# ASD2412.net
KiCad netlist of a schematic drawn in EAGLE
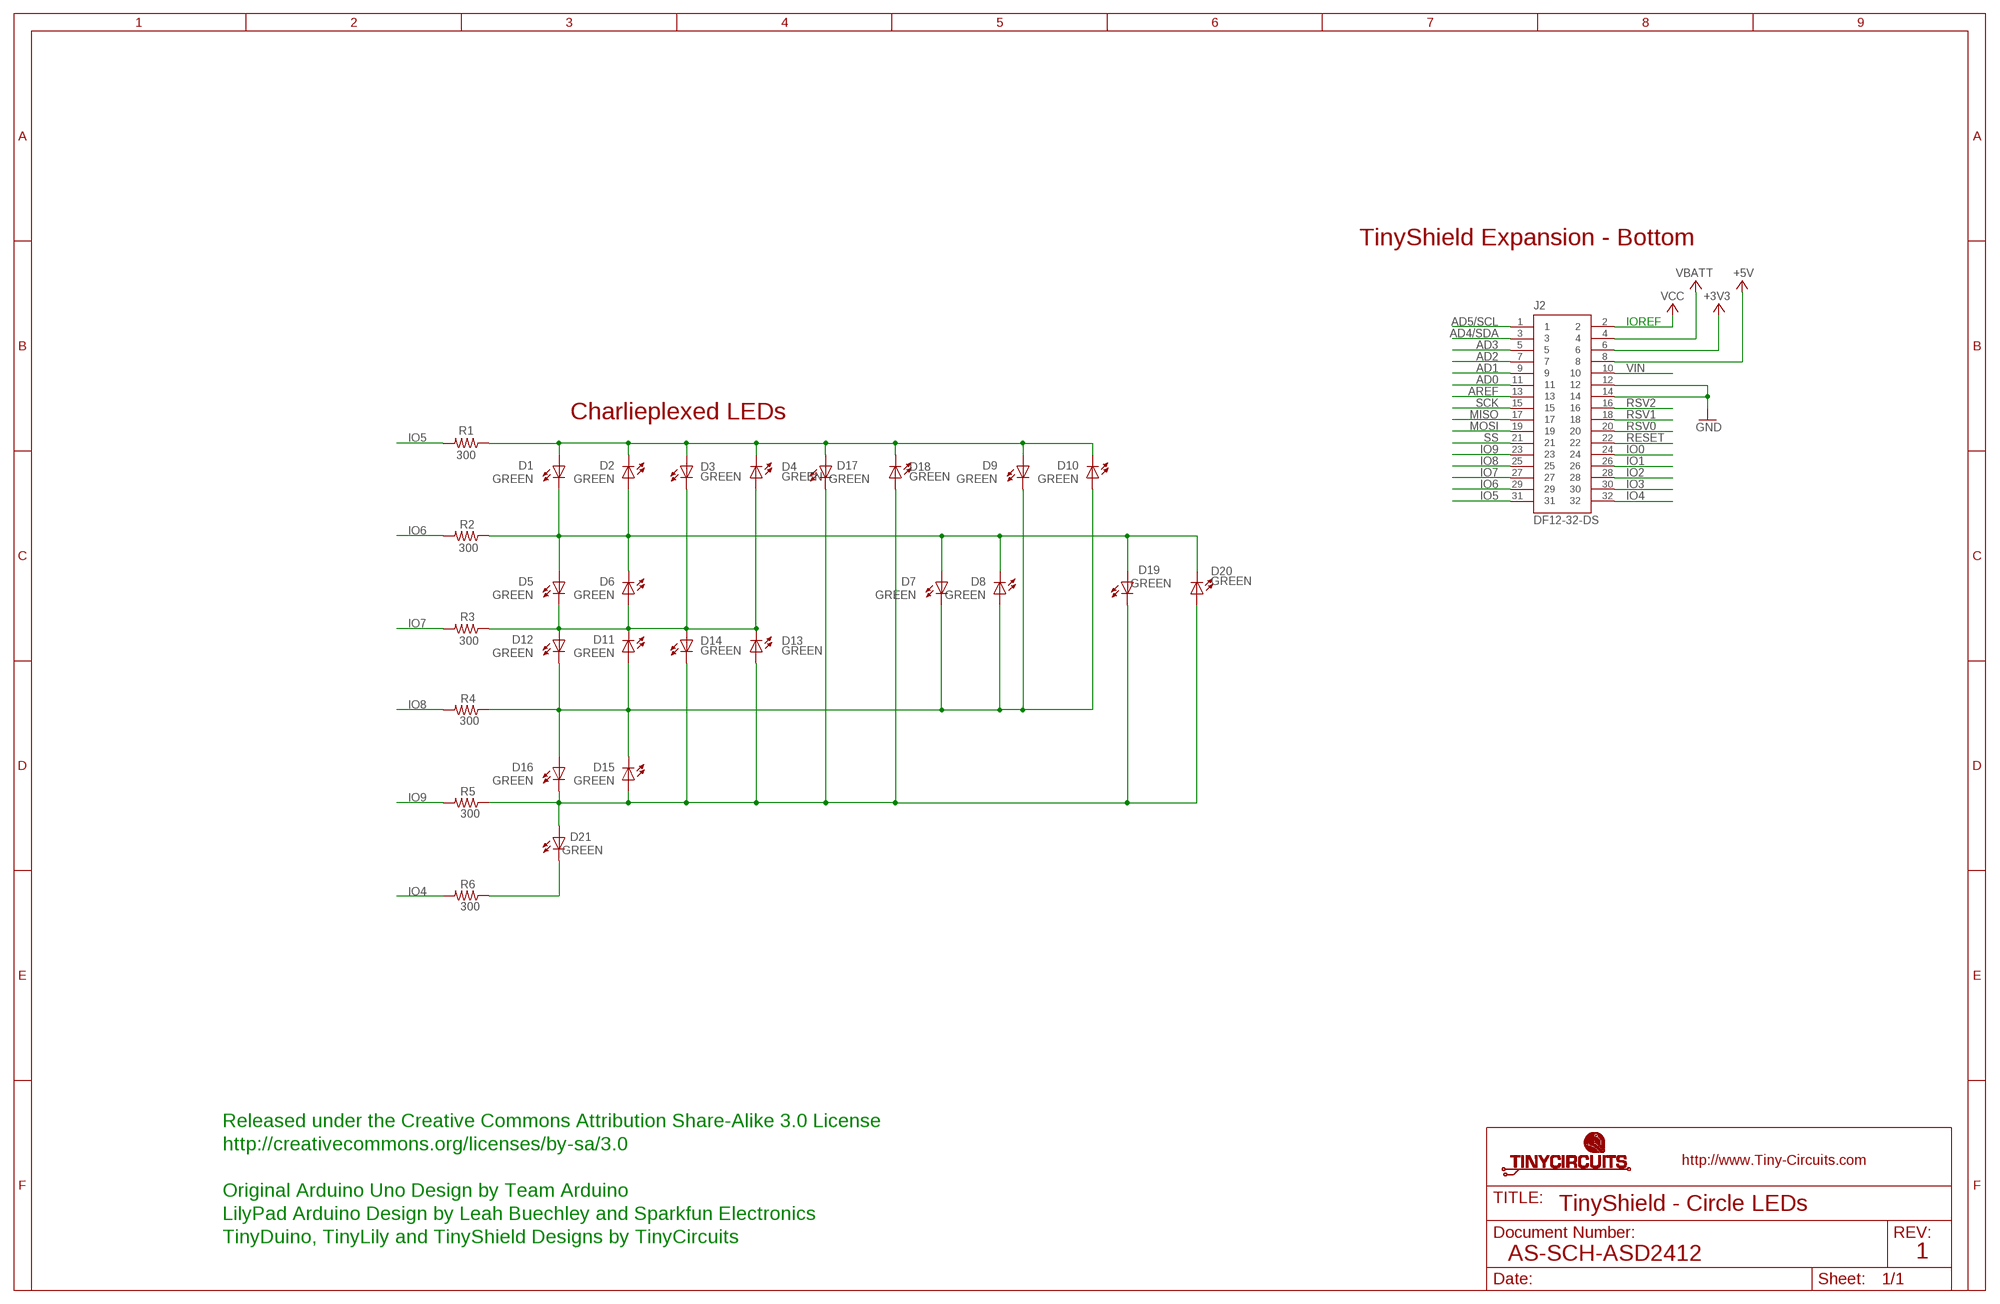
[diagram p0: schematic, sheet 1]

(export (version "E")
  (design (tool "Eeschema 10.0.6"))
  (components
    (comp (ref "D1")
      (value "GREEN")
      (footprint "eagle-import:LNJ_LED")
      (fields (field (name "PARTNO") "AS-ITM-00011") (field (name "PARTNO_1") "AS-ITM-00011"))
      (libsource (lib "eagle-import") (part "AS-ITM-00011"))
    )
    (comp (ref "D2")
      (value "GREEN")
      (footprint "eagle-import:LNJ_LED")
      (fields (field (name "PARTNO") "AS-ITM-00011") (field (name "PARTNO_1") "AS-ITM-00011"))
      (libsource (lib "eagle-import") (part "AS-ITM-00011"))
    )
    (comp (ref "D3")
      (value "GREEN")
      (footprint "eagle-import:LNJ_LED")
      (fields (field (name "PARTNO") "AS-ITM-00011") (field (name "PARTNO_1") "AS-ITM-00011"))
      (libsource (lib "eagle-import") (part "AS-ITM-00011"))
    )
    (comp (ref "D4")
      (value "GREEN")
      (footprint "eagle-import:LNJ_LED")
      (fields (field (name "PARTNO") "AS-ITM-00011") (field (name "PARTNO_1") "AS-ITM-00011"))
      (libsource (lib "eagle-import") (part "AS-ITM-00011"))
    )
    (comp (ref "D5")
      (value "GREEN")
      (footprint "eagle-import:LNJ_LED")
      (fields (field (name "PARTNO") "AS-ITM-00011") (field (name "PARTNO_1") "AS-ITM-00011"))
      (libsource (lib "eagle-import") (part "AS-ITM-00011"))
    )
    (comp (ref "D6")
      (value "GREEN")
      (footprint "eagle-import:LNJ_LED")
      (fields (field (name "PARTNO") "AS-ITM-00011") (field (name "PARTNO_1") "AS-ITM-00011"))
      (libsource (lib "eagle-import") (part "AS-ITM-00011"))
    )
    (comp (ref "D7")
      (value "GREEN")
      (footprint "eagle-import:LNJ_LED")
      (fields (field (name "PARTNO") "AS-ITM-00011") (field (name "PARTNO_1") "AS-ITM-00011"))
      (libsource (lib "eagle-import") (part "AS-ITM-00011"))
    )
    (comp (ref "D8")
      (value "GREEN")
      (footprint "eagle-import:LNJ_LED")
      (fields (field (name "PARTNO") "AS-ITM-00011") (field (name "PARTNO_1") "AS-ITM-00011"))
      (libsource (lib "eagle-import") (part "AS-ITM-00011"))
    )
    (comp (ref "D9")
      (value "GREEN")
      (footprint "eagle-import:LNJ_LED")
      (fields (field (name "PARTNO") "AS-ITM-00011") (field (name "PARTNO_1") "AS-ITM-00011"))
      (libsource (lib "eagle-import") (part "AS-ITM-00011"))
    )
    (comp (ref "D10")
      (value "GREEN")
      (footprint "eagle-import:LNJ_LED")
      (fields (field (name "PARTNO") "AS-ITM-00011") (field (name "PARTNO_1") "AS-ITM-00011"))
      (libsource (lib "eagle-import") (part "AS-ITM-00011"))
    )
    (comp (ref "D11")
      (value "GREEN")
      (footprint "eagle-import:LNJ_LED")
      (fields (field (name "PARTNO") "AS-ITM-00011") (field (name "PARTNO_1") "AS-ITM-00011"))
      (libsource (lib "eagle-import") (part "AS-ITM-00011"))
    )
    (comp (ref "D12")
      (value "GREEN")
      (footprint "eagle-import:LNJ_LED")
      (fields (field (name "PARTNO") "AS-ITM-00011") (field (name "PARTNO_1") "AS-ITM-00011"))
      (libsource (lib "eagle-import") (part "AS-ITM-00011"))
    )
    (comp (ref "D13")
      (value "GREEN")
      (footprint "eagle-import:LNJ_LED")
      (fields (field (name "PARTNO") "AS-ITM-00011") (field (name "PARTNO_1") "AS-ITM-00011"))
      (libsource (lib "eagle-import") (part "AS-ITM-00011"))
    )
    (comp (ref "D14")
      (value "GREEN")
      (footprint "eagle-import:LNJ_LED")
      (fields (field (name "PARTNO") "AS-ITM-00011") (field (name "PARTNO_1") "AS-ITM-00011"))
      (libsource (lib "eagle-import") (part "AS-ITM-00011"))
    )
    (comp (ref "D15")
      (value "GREEN")
      (footprint "eagle-import:LNJ_LED")
      (fields (field (name "PARTNO") "AS-ITM-00011") (field (name "PARTNO_1") "AS-ITM-00011"))
      (libsource (lib "eagle-import") (part "AS-ITM-00011"))
    )
    (comp (ref "D16")
      (value "GREEN")
      (footprint "eagle-import:LNJ_LED")
      (fields (field (name "PARTNO") "AS-ITM-00011") (field (name "PARTNO_1") "AS-ITM-00011"))
      (libsource (lib "eagle-import") (part "AS-ITM-00011"))
    )
    (comp (ref "D17")
      (value "GREEN")
      (footprint "eagle-import:LNJ_LED")
      (fields (field (name "PARTNO") "AS-ITM-00011"))
      (libsource (lib "eagle-import") (part "AS-ITM-00011"))
    )
    (comp (ref "D18")
      (value "GREEN")
      (footprint "eagle-import:LNJ_LED")
      (fields (field (name "PARTNO") "AS-ITM-00011"))
      (libsource (lib "eagle-import") (part "AS-ITM-00011"))
    )
    (comp (ref "D19")
      (value "GREEN")
      (footprint "eagle-import:LNJ_LED")
      (fields (field (name "PARTNO") "AS-ITM-00011"))
      (libsource (lib "eagle-import") (part "AS-ITM-00011"))
    )
    (comp (ref "D20")
      (value "GREEN")
      (footprint "eagle-import:LNJ_LED")
      (fields (field (name "PARTNO") "AS-ITM-00011"))
      (libsource (lib "eagle-import") (part "AS-ITM-00011"))
    )
    (comp (ref "D21")
      (value "GREEN")
      (footprint "eagle-import:LNJ_LED")
      (fields (field (name "PARTNO") "AS-ITM-00011"))
      (libsource (lib "eagle-import") (part "AS-ITM-00011"))
    )
    (comp (ref "J2")
      (value "DF12-32-DS")
      (footprint "eagle-import:DF12-32-DS")
      (fields (field (name "PARTNO") "AS-ITM-00012") (field (name "PARTNO_1") "AS-ITM-00012"))
      (libsource (lib "eagle-import") (part "AS-ITM-00012"))
    )
    (comp (ref "R1")
      (value "300")
      (footprint "eagle-import:0402")
      (fields (field (name "PARTNO") "AS-ITM-00016") (field (name "PARTNO_1") "AS-ITM-00016"))
      (libsource (lib "eagle-import") (part "AS-ITM-00016"))
    )
    (comp (ref "R2")
      (value "300")
      (footprint "eagle-import:0402")
      (fields (field (name "PARTNO") "AS-ITM-00016"))
      (libsource (lib "eagle-import") (part "AS-ITM-00016"))
    )
    (comp (ref "R3")
      (value "300")
      (footprint "eagle-import:0402")
      (fields (field (name "PARTNO") "AS-ITM-00016"))
      (libsource (lib "eagle-import") (part "AS-ITM-00016"))
    )
    (comp (ref "R4")
      (value "300")
      (footprint "eagle-import:0402")
      (fields (field (name "PARTNO") "AS-ITM-00016"))
      (libsource (lib "eagle-import") (part "AS-ITM-00016"))
    )
    (comp (ref "R5")
      (value "300")
      (footprint "eagle-import:0402")
      (fields (field (name "PARTNO") "AS-ITM-00016"))
      (libsource (lib "eagle-import") (part "AS-ITM-00016"))
    )
    (comp (ref "R6")
      (value "300")
      (footprint "eagle-import:0402")
      (fields (field (name "PARTNO") "AS-ITM-00016") (field (name "PARTNO_1") "AS-ITM-00016"))
      (libsource (lib "eagle-import") (part "AS-ITM-00016"))
    )
  )
  (nets
    (net (code "1") (name "+3V3") (class "Default")
      (node (ref "J2") (pin "6") (pinfunction "6_6") (pintype "bidirectional"))
    )
    (net (code "2") (name "+5V") (class "Default")
      (node (ref "J2") (pin "8") (pinfunction "8_8") (pintype "bidirectional"))
    )
    (net (code "3") (name "/AD0") (class "Default")
      (node (ref "J2") (pin "11") (pinfunction "11_11") (pintype "bidirectional"))
    )
    (net (code "4") (name "/AD1") (class "Default")
      (node (ref "J2") (pin "9") (pinfunction "9_9") (pintype "bidirectional"))
    )
    (net (code "5") (name "/AD2") (class "Default")
      (node (ref "J2") (pin "7") (pinfunction "7_7") (pintype "bidirectional"))
    )
    (net (code "6") (name "/AD3") (class "Default")
      (node (ref "J2") (pin "5") (pinfunction "5_5") (pintype "bidirectional"))
    )
    (net (code "7") (name "/AD4{slash}SDA") (class "Default")
      (node (ref "J2") (pin "3") (pinfunction "3_3") (pintype "bidirectional"))
    )
    (net (code "8") (name "/AD5{slash}SCL") (class "Default")
      (node (ref "J2") (pin "1") (pinfunction "1_1") (pintype "bidirectional"))
    )
    (net (code "9") (name "/AREF") (class "Default")
      (node (ref "J2") (pin "13") (pinfunction "13_13") (pintype "bidirectional"))
    )
    (net (code "10") (name "/IO0") (class "Default")
      (node (ref "J2") (pin "24") (pinfunction "24_24") (pintype "bidirectional"))
    )
    (net (code "11") (name "/IO1") (class "Default")
      (node (ref "J2") (pin "26") (pinfunction "26_26") (pintype "bidirectional"))
    )
    (net (code "12") (name "/IO2") (class "Default")
      (node (ref "J2") (pin "28") (pinfunction "28_28") (pintype "bidirectional"))
    )
    (net (code "13") (name "/IO3") (class "Default")
      (node (ref "J2") (pin "30") (pinfunction "30_30") (pintype "bidirectional"))
    )
    (net (code "14") (name "/IO4") (class "Default")
      (node (ref "J2") (pin "32") (pinfunction "32_32") (pintype "bidirectional"))
      (node (ref "R6") (pin "2") (pinfunction "2_2") (pintype "passive"))
    )
    (net (code "15") (name "/IO5") (class "Default")
      (node (ref "J2") (pin "31") (pinfunction "31_31") (pintype "bidirectional"))
      (node (ref "R1") (pin "2") (pinfunction "2_2") (pintype "passive"))
    )
    (net (code "16") (name "/IO6") (class "Default")
      (node (ref "J2") (pin "29") (pinfunction "29_29") (pintype "bidirectional"))
      (node (ref "R2") (pin "2") (pinfunction "2_2") (pintype "passive"))
    )
    (net (code "17") (name "/IO7") (class "Default")
      (node (ref "J2") (pin "27") (pinfunction "27_27") (pintype "bidirectional"))
      (node (ref "R3") (pin "2") (pinfunction "2_2") (pintype "passive"))
    )
    (net (code "18") (name "/IO8") (class "Default")
      (node (ref "J2") (pin "25") (pinfunction "25_25") (pintype "bidirectional"))
      (node (ref "R4") (pin "2") (pinfunction "2_2") (pintype "passive"))
    )
    (net (code "19") (name "/IO9") (class "Default")
      (node (ref "J2") (pin "23") (pinfunction "23_23") (pintype "bidirectional"))
      (node (ref "R5") (pin "2") (pinfunction "2_2") (pintype "passive"))
    )
    (net (code "20") (name "/MISO") (class "Default")
      (node (ref "J2") (pin "17") (pinfunction "17_17") (pintype "bidirectional"))
    )
    (net (code "21") (name "/MOSI") (class "Default")
      (node (ref "J2") (pin "19") (pinfunction "19_19") (pintype "bidirectional"))
    )
    (net (code "22") (name "/RESET") (class "Default")
      (node (ref "J2") (pin "22") (pinfunction "22_22") (pintype "bidirectional"))
    )
    (net (code "23") (name "/RSV0") (class "Default")
      (node (ref "J2") (pin "20") (pinfunction "20_20") (pintype "bidirectional"))
    )
    (net (code "24") (name "/RSV1") (class "Default")
      (node (ref "J2") (pin "18") (pinfunction "18_18") (pintype "bidirectional"))
    )
    (net (code "25") (name "/RSV2") (class "Default")
      (node (ref "J2") (pin "16") (pinfunction "16_16") (pintype "bidirectional"))
    )
    (net (code "26") (name "/SCK") (class "Default")
      (node (ref "J2") (pin "15") (pinfunction "15_15") (pintype "bidirectional"))
    )
    (net (code "27") (name "/SS") (class "Default")
      (node (ref "J2") (pin "21") (pinfunction "21_21") (pintype "bidirectional"))
    )
    (net (code "28") (name "/VIN") (class "Default")
      (node (ref "J2") (pin "10") (pinfunction "10_10") (pintype "bidirectional"))
    )
    (net (code "29") (name "GND") (class "Default")
      (node (ref "J2") (pin "12") (pinfunction "12_12") (pintype "bidirectional"))
      (node (ref "J2") (pin "14") (pinfunction "14_14") (pintype "bidirectional"))
    )
    (net (code "30") (name "Net-(D1-PadA)") (class "Default")
      (node (ref "D1") (pin "A") (pinfunction "A_A") (pintype "passive"))
      (node (ref "D10") (pin "C") (pinfunction "C_C") (pintype "passive"))
      (node (ref "D17") (pin "A") (pinfunction "A_A") (pintype "passive"))
      (node (ref "D18") (pin "C") (pinfunction "C_C") (pintype "passive"))
      (node (ref "D2") (pin "C") (pinfunction "C_C") (pintype "passive"))
      (node (ref "D3") (pin "A") (pinfunction "A_A") (pintype "passive"))
      (node (ref "D4") (pin "C") (pinfunction "C_C") (pintype "passive"))
      (node (ref "D9") (pin "A") (pinfunction "A_A") (pintype "passive"))
      (node (ref "R1") (pin "1") (pinfunction "1_1") (pintype "passive"))
    )
    (net (code "31") (name "Net-(D1-PadC)") (class "Default")
      (node (ref "D1") (pin "C") (pinfunction "C_C") (pintype "passive"))
      (node (ref "D19") (pin "A") (pinfunction "A_A") (pintype "passive"))
      (node (ref "D2") (pin "A") (pinfunction "A_A") (pintype "passive"))
      (node (ref "D20") (pin "C") (pinfunction "C_C") (pintype "passive"))
      (node (ref "D5") (pin "A") (pinfunction "A_A") (pintype "passive"))
      (node (ref "D6") (pin "C") (pinfunction "C_C") (pintype "passive"))
      (node (ref "D7") (pin "A") (pinfunction "A_A") (pintype "passive"))
      (node (ref "D8") (pin "C") (pinfunction "C_C") (pintype "passive"))
      (node (ref "R2") (pin "1") (pinfunction "1_1") (pintype "passive"))
    )
    (net (code "32") (name "Net-(D10-PadA)") (class "Default")
      (node (ref "D10") (pin "A") (pinfunction "A_A") (pintype "passive"))
      (node (ref "D11") (pin "A") (pinfunction "A_A") (pintype "passive"))
      (node (ref "D12") (pin "C") (pinfunction "C_C") (pintype "passive"))
      (node (ref "D15") (pin "C") (pinfunction "C_C") (pintype "passive"))
      (node (ref "D16") (pin "A") (pinfunction "A_A") (pintype "passive"))
      (node (ref "D7") (pin "C") (pinfunction "C_C") (pintype "passive"))
      (node (ref "D8") (pin "A") (pinfunction "A_A") (pintype "passive"))
      (node (ref "D9") (pin "C") (pinfunction "C_C") (pintype "passive"))
      (node (ref "R4") (pin "1") (pinfunction "1_1") (pintype "passive"))
    )
    (net (code "33") (name "Net-(D11-PadC)") (class "Default")
      (node (ref "D11") (pin "C") (pinfunction "C_C") (pintype "passive"))
      (node (ref "D12") (pin "A") (pinfunction "A_A") (pintype "passive"))
      (node (ref "D13") (pin "C") (pinfunction "C_C") (pintype "passive"))
      (node (ref "D14") (pin "A") (pinfunction "A_A") (pintype "passive"))
      (node (ref "D3") (pin "C") (pinfunction "C_C") (pintype "passive"))
      (node (ref "D4") (pin "A") (pinfunction "A_A") (pintype "passive"))
      (node (ref "D5") (pin "C") (pinfunction "C_C") (pintype "passive"))
      (node (ref "D6") (pin "A") (pinfunction "A_A") (pintype "passive"))
      (node (ref "R3") (pin "1") (pinfunction "1_1") (pintype "passive"))
    )
    (net (code "34") (name "Net-(D13-PadA)") (class "Default")
      (node (ref "D13") (pin "A") (pinfunction "A_A") (pintype "passive"))
      (node (ref "D14") (pin "C") (pinfunction "C_C") (pintype "passive"))
      (node (ref "D15") (pin "A") (pinfunction "A_A") (pintype "passive"))
      (node (ref "D16") (pin "C") (pinfunction "C_C") (pintype "passive"))
      (node (ref "D17") (pin "C") (pinfunction "C_C") (pintype "passive"))
      (node (ref "D18") (pin "A") (pinfunction "A_A") (pintype "passive"))
      (node (ref "D19") (pin "C") (pinfunction "C_C") (pintype "passive"))
      (node (ref "D20") (pin "A") (pinfunction "A_A") (pintype "passive"))
      (node (ref "D21") (pin "A") (pinfunction "A_A") (pintype "passive"))
      (node (ref "R5") (pin "1") (pinfunction "1_1") (pintype "passive"))
    )
    (net (code "35") (name "Net-(D21-PadC)") (class "Default")
      (node (ref "D21") (pin "C") (pinfunction "C_C") (pintype "passive"))
      (node (ref "R6") (pin "1") (pinfunction "1_1") (pintype "passive"))
    )
    (net (code "36") (name "VBATT") (class "Default")
      (node (ref "J2") (pin "4") (pinfunction "4_4") (pintype "bidirectional"))
    )
    (net (code "37") (name "VCC") (class "Default")
      (node (ref "J2") (pin "2") (pinfunction "2_2") (pintype "bidirectional"))
    )
  )
)
